# ESP32_Schematic.net
KiCad netlist of a schematic drawn in Altium Designer
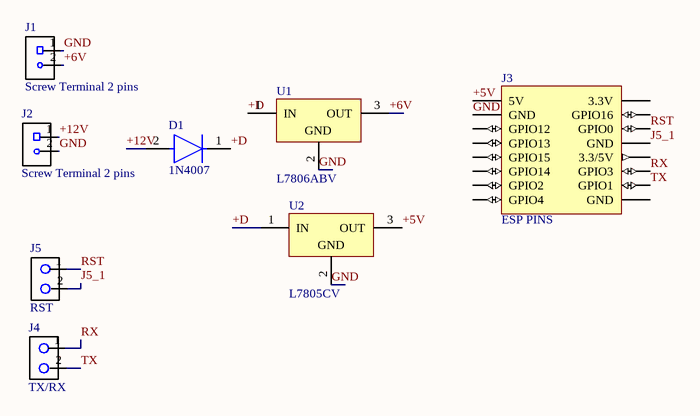
[diagram p0: ESP32 Schematic.SchDoc]

(export (version "E")
  (design (tool "Eeschema 10.0.6"))
  (components
    (comp (ref "D1")
      (value "1N4007")
      (footprint "FP-1N4007-MFG")
      (description "Rectifier diode 1000 V 1 A DO-41, ,")
      (fields
        (field (name "MANUFACTURER") "Diotec")
        (field (name "OCTOPART") "https://octopart.com/1n4007-diotec-4040411")
      )
      (libsource (lib "Altium Content Vault") (part "d7152d700b627762746794eb795d46e"))
    )
    (comp (ref "J1")
      (value "Screw Terminal 2 pins")
      (footprint "Screw Terminal 2 pins")
      (fields (field (name "MANUFACTURER") "CUI") (field (name "MANUFACTURER PART NUMBER") "TB004-508-02BE"))
      (libsource (lib "SCH_LIB2SchLib") (part "Screw Terminal 2 pins"))
    )
    (comp (ref "J2")
      (value "Screw Terminal 2 pins")
      (footprint "Screw Terminal 2 pins")
      (fields (field (name "MANUFACTURER") "CUI") (field (name "MANUFACTURER PART NUMBER") "TB004-508-02BE"))
      (libsource (lib "SCH_LIB2SchLib") (part "Screw Terminal 2 pins"))
    )
    (comp (ref "J3")
      (value "ESP PINS")
      (footprint "ESP32 CAM")
      (libsource (lib "SCH_LIB2SchLib") (part "ESP PINS"))
    )
    (comp (ref "J4")
      (value "TX/RX")
      (footprint "Pin Header 1x2")
      (libsource (lib "SCH_LIB2SchLib") (part "Pin Header 1x2"))
    )
    (comp (ref "J5")
      (value "RST")
      (footprint "Pin Header 1x2")
      (libsource (lib "SCH_LIB2SchLib") (part "Pin Header 1x2"))
    )
    (comp (ref "U1")
      (value "L7806ABV")
      (footprint "TO220")
      (description "Positive Voltage Regulator, 6V, 3-Pin TO-220")
      (libsource (lib "Altium Content Vault") (part "PM-REG-L4940-SIL3"))
    )
    (comp (ref "U2")
      (value "L7805CV")
      (footprint "TO220")
      (description "Positive Voltage Regulator, 5V, 3-Pin TO-220")
      (libsource (lib "Altium Content Vault") (part "PM-REG-L4940-SIL3"))
    )
  )
  (nets
    (net (code "1") (name "/+5V") (class "Default")
      (node (ref "J3") (pin "5V") (pinfunction "5V_5V") (pintype "power_in"))
      (node (ref "U2") (pin "3") (pinfunction "OUT_3") (pintype "power_in"))
    )
    (net (code "2") (name "/+6V") (class "Default")
      (node (ref "J1") (pin "2") (pintype "passive"))
      (node (ref "U1") (pin "3") (pinfunction "OUT_3") (pintype "power_in"))
    )
    (net (code "3") (name "/+12V") (class "Default")
      (node (ref "D1") (pin "2") (pinfunction "A_2") (pintype "passive"))
      (node (ref "J2") (pin "1") (pinfunction "1_1") (pintype "passive"))
    )
    (net (code "4") (name "/+D") (class "Default")
      (node (ref "D1") (pin "1") (pinfunction "C_1") (pintype "passive"))
      (node (ref "U1") (pin "1") (pinfunction "IN_1") (pintype "power_in"))
      (node (ref "U2") (pin "1") (pinfunction "IN_1") (pintype "power_in"))
    )
    (net (code "5") (name "/GND") (class "Default")
      (node (ref "J1") (pin "1") (pinfunction "1_1") (pintype "passive"))
      (node (ref "J2") (pin "2") (pintype "passive"))
      (node (ref "J3") (pin "GND") (pinfunction "GND_GND") (pintype "power_in"))
      (node (ref "U1") (pin "2") (pinfunction "GND_2") (pintype "power_in"))
      (node (ref "U2") (pin "2") (pinfunction "GND_2") (pintype "power_in"))
    )
    (net (code "6") (name "/J5_1") (class "Default")
      (node (ref "J3") (pin "GNDR") (pinfunction "GND_GNDR") (pintype "power_in"))
      (node (ref "J5") (pin "2") (pinfunction "2_2") (pintype "passive"))
    )
    (net (code "7") (name "/RST") (class "Default")
      (node (ref "J3") (pin "0") (pinfunction "GPIO0_0") (pintype "bidirectional"))
      (node (ref "J5") (pin "1") (pinfunction "1_1") (pintype "passive"))
    )
    (net (code "8") (name "/RX") (class "Default")
      (node (ref "J3") (pin "3") (pinfunction "GPIO3_3") (pintype "bidirectional"))
      (node (ref "J4") (pin "1") (pinfunction "1_1") (pintype "passive"))
    )
    (net (code "9") (name "/TX") (class "Default")
      (node (ref "J3") (pin "1") (pinfunction "GPIO1_1") (pintype "bidirectional"))
      (node (ref "J4") (pin "2") (pinfunction "2_2") (pintype "passive"))
    )
    (net (code "10") (name "unconnected-(J3-GND-PadGRND)") (class "Default")
      (node (ref "J3") (pin "GRND") (pinfunction "GND_GRND") (pintype "power_in"))
    )
    (net (code "11") (name "unconnected-(J3-GPIO2-Pad2)") (class "Default")
      (node (ref "J3") (pin "2") (pinfunction "GPIO2_2") (pintype "bidirectional"))
    )
    (net (code "12") (name "unconnected-(J3-GPIO4-Pad4)") (class "Default")
      (node (ref "J3") (pin "4") (pinfunction "GPIO4_4") (pintype "bidirectional"))
    )
    (net (code "13") (name "unconnected-(J3-GPIO12-Pad12)") (class "Default")
      (node (ref "J3") (pin "12") (pinfunction "GPIO12_12") (pintype "bidirectional"))
    )
    (net (code "14") (name "unconnected-(J3-GPIO13-Pad13)") (class "Default")
      (node (ref "J3") (pin "13") (pinfunction "GPIO13_13") (pintype "bidirectional"))
    )
    (net (code "15") (name "unconnected-(J3-GPIO14-Pad14)") (class "Default")
      (node (ref "J3") (pin "14") (pinfunction "GPIO14_14") (pintype "bidirectional"))
    )
    (net (code "16") (name "unconnected-(J3-GPIO15-Pad15)") (class "Default")
      (node (ref "J3") (pin "15") (pinfunction "GPIO15_15") (pintype "bidirectional"))
    )
    (net (code "17") (name "unconnected-(J3-GPIO16-Pad16)") (class "Default")
      (node (ref "J3") (pin "16") (pinfunction "GPIO16_16") (pintype "bidirectional"))
    )
    (net (code "18") (name "unconnected-(J3-Pad3.3V)") (class "Default")
      (node (ref "J3") (pin "3.3V") (pinfunction "3.3V_3.3V") (pintype "power_in"))
    )
    (net (code "19") (name "unconnected-(J3-Pad3.3{slash}5V)") (class "Default")
      (node (ref "J3") (pin "3.3/5V") (pinfunction "3.3/5V_3.3/5V") (pintype "output"))
    )
  )
)
